# MainBoard.net
KiCad netlist of a schematic drawn in EAGLE
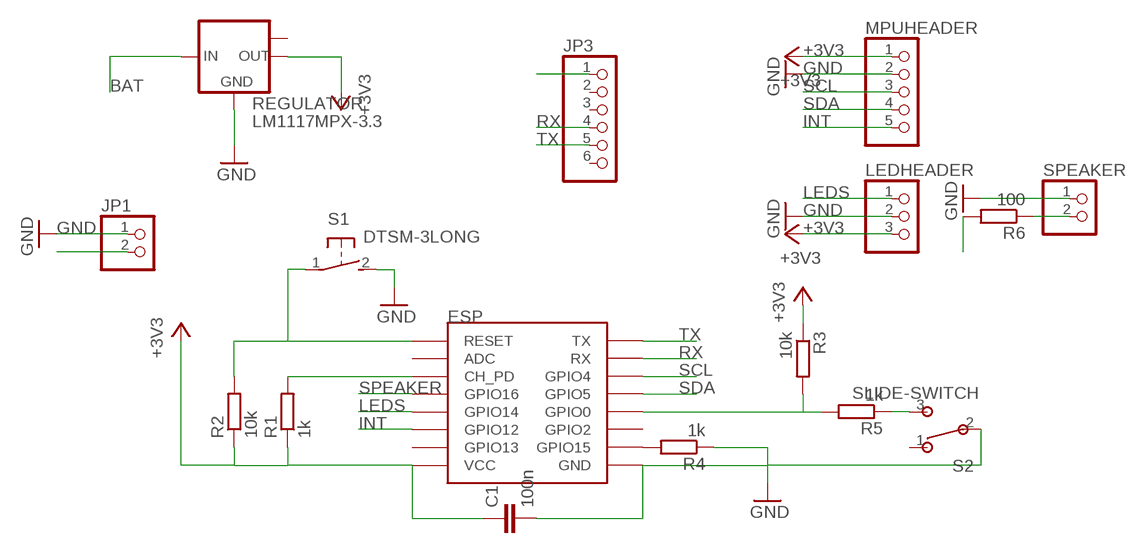
[diagram p0: schematic, sheet 1]

(export (version "E")
  (design (tool "Eeschema 10.0.6"))
  (components
    (comp (ref "C1")
      (value "100n")
      (footprint "eagle-import:C1206")
      (libsource (lib "eagle-import") (part "C-EUC1206"))
    )
    (comp (ref "ESP")
      (value "ESP12SMD")
      (footprint "eagle-import:ESP12-SMD")
      (libsource (lib "eagle-import") (part "ESP12SMD"))
    )
    (comp (ref "JP1")
      (value "PINHD-1X2")
      (footprint "eagle-import:1X02")
      (libsource (lib "eagle-import") (part "PINHD-1X2"))
    )
    (comp (ref "JP3")
      (value "PINHD-1X6")
      (footprint "eagle-import:1X06")
      (libsource (lib "eagle-import") (part "PINHD-1X6"))
    )
    (comp (ref "LEDHEADER")
      (value "PINHD-1X3")
      (footprint "eagle-import:1X03")
      (libsource (lib "eagle-import") (part "PINHD-1X3"))
    )
    (comp (ref "MPUHEADER")
      (value "PINHD-1X5")
      (footprint "eagle-import:1X05")
      (libsource (lib "eagle-import") (part "PINHD-1X5"))
    )
    (comp (ref "R1")
      (value "1k")
      (footprint "eagle-import:R1206")
      (libsource (lib "eagle-import") (part "R-EU_R1206"))
    )
    (comp (ref "R2")
      (value "10k")
      (footprint "eagle-import:R1206")
      (libsource (lib "eagle-import") (part "R-EU_R1206"))
    )
    (comp (ref "R3")
      (value "10k")
      (footprint "eagle-import:R1206")
      (libsource (lib "eagle-import") (part "R-EU_R1206"))
    )
    (comp (ref "R4")
      (value "1k")
      (footprint "eagle-import:R1206")
      (libsource (lib "eagle-import") (part "R-EU_R1206"))
    )
    (comp (ref "R5")
      (value "1k")
      (footprint "eagle-import:R1206")
      (libsource (lib "eagle-import") (part "R-EU_R1206"))
    )
    (comp (ref "R6")
      (value "100")
      (footprint "eagle-import:R1206")
      (libsource (lib "eagle-import") (part "R-EU_R1206"))
    )
    (comp (ref "REGULATOR")
      (value "LM1117MPX-3.3")
      (footprint "eagle-import:SOT223")
      (libsource (lib "eagle-import") (part "LM1117MPX-3.3"))
    )
    (comp (ref "S1")
      (value "DTSM-3LONG")
      (footprint "eagle-import:DTSM-3LONG")
      (libsource (lib "eagle-import") (part "DTSM-3LONG"))
    )
    (comp (ref "S2")
      (value "SLIDE-SWITCH")
      (footprint "eagle-import:AYZ0102AGRLC")
      (libsource (lib "eagle-import") (part "SLIDE-SWITCH"))
    )
    (comp (ref "SPEAKER")
      (value "PINHD-1X2")
      (footprint "eagle-import:1X02")
      (libsource (lib "eagle-import") (part "PINHD-1X2"))
    )
  )
  (nets
    (net (code "1") (name "+3V3") (class "Default")
      (node (ref "C1") (pin "1") (pinfunction "1_1") (pintype "passive"))
      (node (ref "ESP") (pin "VCC") (pinfunction "VCC_VCC") (pintype "bidirectional"))
      (node (ref "LEDHEADER") (pin "3") (pinfunction "3_3") (pintype "passive"))
      (node (ref "MPUHEADER") (pin "1") (pinfunction "1_1") (pintype "passive"))
      (node (ref "R1") (pin "1") (pinfunction "1_1") (pintype "passive"))
      (node (ref "R2") (pin "1") (pinfunction "1_1") (pintype "passive"))
      (node (ref "R3") (pin "1") (pinfunction "1_1") (pintype "passive"))
      (node (ref "REGULATOR") (pin "2") (pinfunction "OUT_2") (pintype "passive"))
    )
    (net (code "2") (name "/BAT") (class "Default")
      (node (ref "JP1") (pin "2") (pinfunction "2_2") (pintype "passive"))
      (node (ref "REGULATOR") (pin "3") (pinfunction "IN_3") (pintype "input"))
    )
    (net (code "3") (name "/INT") (class "Default")
      (node (ref "ESP") (pin "GPIO12") (pinfunction "GPIO12_GPIO12") (pintype "bidirectional"))
      (node (ref "MPUHEADER") (pin "5") (pinfunction "5_5") (pintype "passive"))
    )
    (net (code "4") (name "/LEDS") (class "Default")
      (node (ref "ESP") (pin "GPIO14") (pinfunction "GPIO14_GPIO14") (pintype "bidirectional"))
      (node (ref "LEDHEADER") (pin "1") (pinfunction "1_1") (pintype "passive"))
    )
    (net (code "5") (name "/RX") (class "Default")
      (node (ref "ESP") (pin "RXD0") (pinfunction "RX_RXD0") (pintype "bidirectional"))
      (node (ref "JP3") (pin "4") (pinfunction "4_4") (pintype "passive"))
    )
    (net (code "6") (name "/SCL") (class "Default")
      (node (ref "ESP") (pin "GPIO4") (pinfunction "GPIO4_GPIO4") (pintype "bidirectional"))
      (node (ref "MPUHEADER") (pin "3") (pinfunction "3_3") (pintype "passive"))
    )
    (net (code "7") (name "/SDA") (class "Default")
      (node (ref "ESP") (pin "GPIO5") (pinfunction "GPIO5_GPIO5") (pintype "bidirectional"))
      (node (ref "MPUHEADER") (pin "4") (pinfunction "4_4") (pintype "passive"))
    )
    (net (code "8") (name "/SPEAKER") (class "Default")
      (node (ref "ESP") (pin "GPIO16") (pinfunction "GPIO16_GPIO16") (pintype "bidirectional"))
      (node (ref "R6") (pin "2") (pinfunction "2_2") (pintype "passive"))
    )
    (net (code "9") (name "/TX") (class "Default")
      (node (ref "ESP") (pin "TXD0") (pinfunction "TX_TXD0") (pintype "bidirectional"))
      (node (ref "JP3") (pin "5") (pinfunction "5_5") (pintype "passive"))
    )
    (net (code "10") (name "GND") (class "Default")
      (node (ref "C1") (pin "2") (pinfunction "2_2") (pintype "passive"))
      (node (ref "ESP") (pin "GND") (pinfunction "GND_GND") (pintype "bidirectional"))
      (node (ref "JP1") (pin "1") (pinfunction "1_1") (pintype "passive"))
      (node (ref "JP3") (pin "1") (pinfunction "1_1") (pintype "passive"))
      (node (ref "LEDHEADER") (pin "2") (pinfunction "2_2") (pintype "passive"))
      (node (ref "MPUHEADER") (pin "2") (pinfunction "2_2") (pintype "passive"))
      (node (ref "R4") (pin "1") (pinfunction "1_1") (pintype "passive"))
      (node (ref "REGULATOR") (pin "1") (pinfunction "GND_1") (pintype "input"))
      (node (ref "S1") (pin "2") (pinfunction "2_2") (pintype "passive"))
      (node (ref "S2") (pin "2") (pinfunction "2_2") (pintype "bidirectional"))
      (node (ref "SPEAKER") (pin "1") (pinfunction "1_1") (pintype "passive"))
    )
    (net (code "11") (name "Net-(ESP-PadCH_PD)") (class "Default")
      (node (ref "ESP") (pin "CH_PD") (pinfunction "CH_PD_CH_PD") (pintype "bidirectional"))
      (node (ref "R1") (pin "2") (pinfunction "2_2") (pintype "passive"))
    )
    (net (code "12") (name "Net-(ESP-PadGPIO0)") (class "Default")
      (node (ref "ESP") (pin "GPIO0") (pinfunction "GPIO0_GPIO0") (pintype "bidirectional"))
      (node (ref "R3") (pin "2") (pinfunction "2_2") (pintype "passive"))
      (node (ref "R5") (pin "2") (pinfunction "2_2") (pintype "passive"))
    )
    (net (code "13") (name "Net-(ESP-PadGPIO15)") (class "Default")
      (node (ref "ESP") (pin "GPIO15") (pinfunction "GPIO15_GPIO15") (pintype "bidirectional"))
      (node (ref "R4") (pin "2") (pinfunction "2_2") (pintype "passive"))
    )
    (net (code "14") (name "Net-(ESP-PadRESET)") (class "Default")
      (node (ref "ESP") (pin "RESET") (pinfunction "RESET_RESET") (pintype "bidirectional"))
      (node (ref "R2") (pin "2") (pinfunction "2_2") (pintype "passive"))
      (node (ref "S1") (pin "1") (pinfunction "1_1") (pintype "passive"))
    )
    (net (code "15") (name "Net-(R5-Pad1)") (class "Default")
      (node (ref "R5") (pin "1") (pinfunction "1_1") (pintype "passive"))
      (node (ref "S2") (pin "3") (pinfunction "3_3") (pintype "bidirectional"))
    )
    (net (code "16") (name "Net-(R6-Pad1)") (class "Default")
      (node (ref "R6") (pin "1") (pinfunction "1_1") (pintype "passive"))
      (node (ref "SPEAKER") (pin "2") (pinfunction "2_2") (pintype "passive"))
    )
    (net (code "17") (name "unconnected-(ESP-PadADC)") (class "Default")
      (node (ref "ESP") (pin "ADC") (pinfunction "ADC_ADC") (pintype "bidirectional"))
    )
    (net (code "18") (name "unconnected-(ESP-PadGPIO2)") (class "Default")
      (node (ref "ESP") (pin "GPIO2") (pinfunction "GPIO2_GPIO2") (pintype "bidirectional"))
    )
    (net (code "19") (name "unconnected-(ESP-PadGPIO13)") (class "Default")
      (node (ref "ESP") (pin "GPIO13") (pinfunction "GPIO13_GPIO13") (pintype "bidirectional"))
    )
    (net (code "20") (name "unconnected-(JP3-Pad2)") (class "Default")
      (node (ref "JP3") (pin "2") (pinfunction "2_2") (pintype "passive"))
    )
    (net (code "21") (name "unconnected-(JP3-Pad3)") (class "Default")
      (node (ref "JP3") (pin "3") (pinfunction "3_3") (pintype "passive"))
    )
    (net (code "22") (name "unconnected-(JP3-Pad6)") (class "Default")
      (node (ref "JP3") (pin "6") (pinfunction "6_6") (pintype "passive"))
    )
    (net (code "23") (name "unconnected-(REGULATOR-OUT1-PadTAB)") (class "Default")
      (node (ref "REGULATOR") (pin "TAB") (pinfunction "OUT1_TAB") (pintype "passive"))
    )
    (net (code "24") (name "unconnected-(S2-Pad1)") (class "Default")
      (node (ref "S2") (pin "1") (pinfunction "1_1") (pintype "bidirectional"))
    )
  )
)
